# transceiver.net
KiCad netlist of a schematic drawn in EAGLE
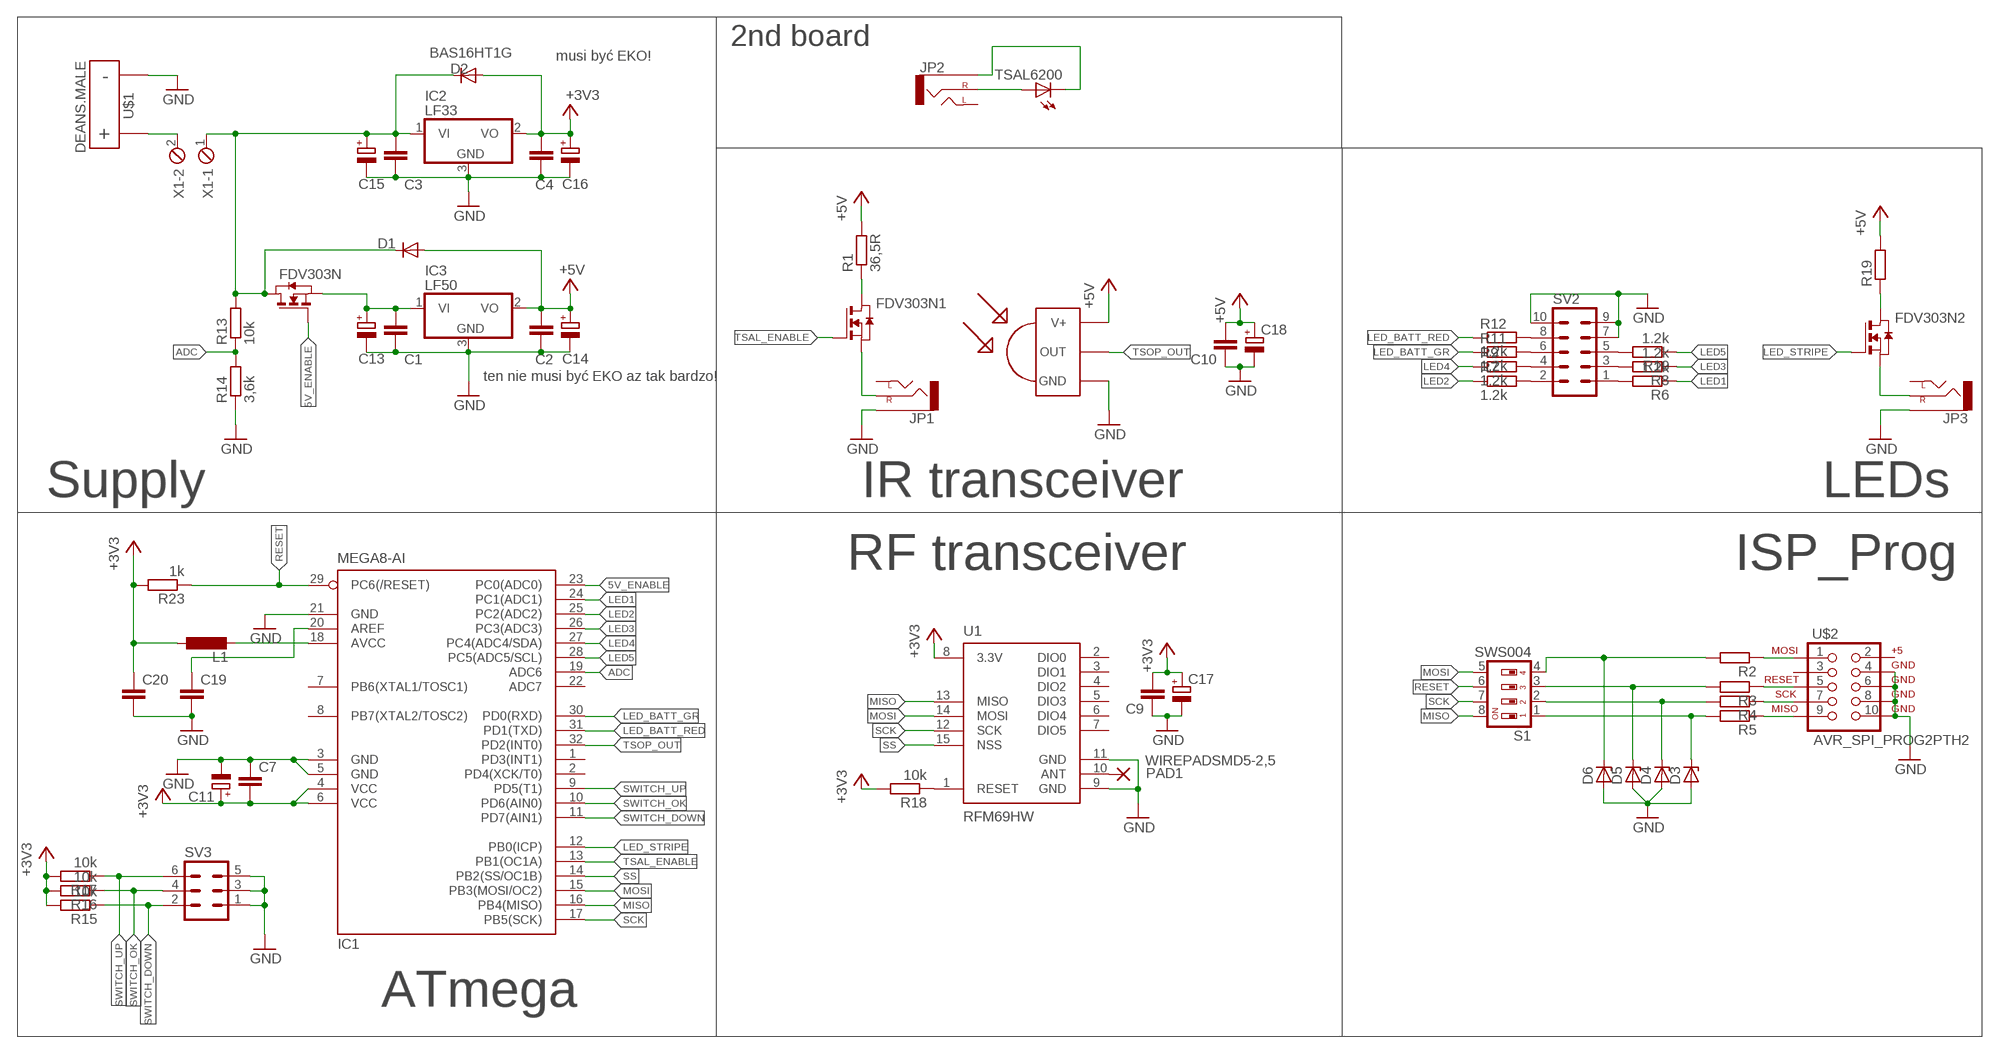
[diagram p0: schematic, sheet 1]

(export (version "E")
  (design (tool "Eeschema 10.0.6"))
  (components
    (comp (ref "C1")
      (value "C-EUC0805")
      (footprint "eagle-import:C0805")
      (libsource (lib "eagle-import") (part "C-EUC0805"))
    )
    (comp (ref "C2")
      (value "C-EUC0805")
      (footprint "eagle-import:C0805")
      (libsource (lib "eagle-import") (part "C-EUC0805"))
    )
    (comp (ref "C3")
      (value "C-EUC0805")
      (footprint "eagle-import:C0805")
      (libsource (lib "eagle-import") (part "C-EUC0805"))
    )
    (comp (ref "C4")
      (value "C-EUC0805")
      (footprint "eagle-import:C0805")
      (libsource (lib "eagle-import") (part "C-EUC0805"))
    )
    (comp (ref "C7")
      (value "C-EUC0805")
      (footprint "eagle-import:C0805")
      (libsource (lib "eagle-import") (part "C-EUC0805"))
    )
    (comp (ref "C9")
      (value "C-EUC0805")
      (footprint "eagle-import:C0805")
      (libsource (lib "eagle-import") (part "C-EUC0805"))
    )
    (comp (ref "C10")
      (value "C-EUC0805")
      (footprint "eagle-import:C0805")
      (libsource (lib "eagle-import") (part "C-EUC0805"))
    )
    (comp (ref "C11")
      (value "CPOL-EUE2.5-5")
      (footprint "eagle-import:E2,5-5")
      (libsource (lib "eagle-import") (part "CPOL-EUE2.5-5"))
    )
    (comp (ref "C13")
      (value "CPOL-EUE2.5-5")
      (footprint "eagle-import:E2,5-5")
      (libsource (lib "eagle-import") (part "CPOL-EUE2.5-5"))
    )
    (comp (ref "C14")
      (value "CPOL-EUE2.5-5")
      (footprint "eagle-import:E2,5-5")
      (libsource (lib "eagle-import") (part "CPOL-EUE2.5-5"))
    )
    (comp (ref "C15")
      (value "CPOL-EUE2.5-5")
      (footprint "eagle-import:E2,5-5")
      (libsource (lib "eagle-import") (part "CPOL-EUE2.5-5"))
    )
    (comp (ref "C16")
      (value "CPOL-EUE2.5-5")
      (footprint "eagle-import:E2,5-5")
      (libsource (lib "eagle-import") (part "CPOL-EUE2.5-5"))
    )
    (comp (ref "C17")
      (value "CPOL-EUE2.5-5")
      (footprint "eagle-import:E2,5-5")
      (libsource (lib "eagle-import") (part "CPOL-EUE2.5-5"))
    )
    (comp (ref "C18")
      (value "CPOL-EUE2.5-5")
      (footprint "eagle-import:E2,5-5")
      (libsource (lib "eagle-import") (part "CPOL-EUE2.5-5"))
    )
    (comp (ref "C19")
      (value "C-EUC0805")
      (footprint "eagle-import:C0805")
      (libsource (lib "eagle-import") (part "C-EUC0805"))
    )
    (comp (ref "C20")
      (value "C-EUC0805")
      (footprint "eagle-import:C0805")
      (libsource (lib "eagle-import") (part "C-EUC0805"))
    )
    (comp (ref "D1")
      (value "BAS16HT1G")
      (footprint "eagle-import:SOD-323")
      (libsource (lib "eagle-import") (part "DIODESOD"))
    )
    (comp (ref "D2")
      (value "BAS16HT1G")
      (footprint "eagle-import:SOD-323")
      (libsource (lib "eagle-import") (part "DIODESOD"))
    )
    (comp (ref "D3")
      (value "ZENER-DIODESOD80C")
      (footprint "eagle-import:SOD80C")
      (libsource (lib "eagle-import") (part "ZENER-DIODESOD80C"))
    )
    (comp (ref "D4")
      (value "ZENER-DIODESOD80C")
      (footprint "eagle-import:SOD80C")
      (libsource (lib "eagle-import") (part "ZENER-DIODESOD80C"))
    )
    (comp (ref "D5")
      (value "ZENER-DIODESOD80C")
      (footprint "eagle-import:SOD80C")
      (libsource (lib "eagle-import") (part "ZENER-DIODESOD80C"))
    )
    (comp (ref "D6")
      (value "ZENER-DIODESOD80C")
      (footprint "eagle-import:SOD80C")
      (libsource (lib "eagle-import") (part "ZENER-DIODESOD80C"))
    )
    (comp (ref "FDV303N")
      (value "NMOSSOT23")
      (footprint "eagle-import:SOT-23")
      (libsource (lib "eagle-import") (part "NMOSSOT23"))
    )
    (comp (ref "FDV303N1")
      (value "NMOSSOT23")
      (footprint "eagle-import:SOT-23")
      (libsource (lib "eagle-import") (part "NMOSSOT23"))
    )
    (comp (ref "FDV303N2")
      (value "NMOSSOT23")
      (footprint "eagle-import:SOT-23")
      (libsource (lib "eagle-import") (part "NMOSSOT23"))
    )
    (comp (ref "IC1")
      (value "MEGA8-AI")
      (footprint "eagle-import:TQFP32-08")
      (fields (field (name "MPN") "ATMEGA8-16AU"))
      (libsource (lib "eagle-import") (part "MEGA8-AI"))
    )
    (comp (ref "IC2")
      (value "LF33")
      (footprint "eagle-import:TO252")
      (libsource (lib "eagle-import") (part "78DT05"))
    )
    (comp (ref "IC3")
      (value "LF50")
      (footprint "eagle-import:TO252")
      (libsource (lib "eagle-import") (part "78DT05"))
    )
    (comp (ref "JP1")
      (value "AUDIO-JACKPTH")
      (footprint "eagle-import:AUDIO-JACK")
      (libsource (lib "eagle-import") (part "AUDIO-JACKPTH"))
    )
    (comp (ref "JP2")
      (value "AUDIO-JACKPTH")
      (footprint "eagle-import:AUDIO-JACK")
      (libsource (lib "eagle-import") (part "AUDIO-JACKPTH"))
    )
    (comp (ref "JP3")
      (value "AUDIO-JACKPTH")
      (footprint "eagle-import:AUDIO-JACK")
      (libsource (lib "eagle-import") (part "AUDIO-JACKPTH"))
    )
    (comp (ref "L1")
      (value "L-EU0204V")
      (footprint "eagle-import:0204V")
      (libsource (lib "eagle-import") (part "L-EU0204V"))
    )
    (comp (ref "PAD1")
      (value "WIREPADSMD5-2,5")
      (footprint "eagle-import:5-2,5")
      (libsource (lib "eagle-import") (part "WIREPADSMD5-2,5"))
    )
    (comp (ref "R1")
      (value "36,5R")
      (footprint "eagle-import:R0805")
      (libsource (lib "eagle-import") (part "R-EU_R0805"))
    )
    (comp (ref "R2")
      (value "R-EU_R0805")
      (footprint "eagle-import:R0805")
      (libsource (lib "eagle-import") (part "R-EU_R0805"))
    )
    (comp (ref "R3")
      (value "R-EU_R0805")
      (footprint "eagle-import:R0805")
      (libsource (lib "eagle-import") (part "R-EU_R0805"))
    )
    (comp (ref "R4")
      (value "R-EU_R0805")
      (footprint "eagle-import:R0805")
      (libsource (lib "eagle-import") (part "R-EU_R0805"))
    )
    (comp (ref "R5")
      (value "R-EU_R0805")
      (footprint "eagle-import:R0805")
      (libsource (lib "eagle-import") (part "R-EU_R0805"))
    )
    (comp (ref "R6")
      (value "1.2k")
      (footprint "eagle-import:R0805")
      (libsource (lib "eagle-import") (part "R-EU_R0805"))
    )
    (comp (ref "R7")
      (value "1.2k")
      (footprint "eagle-import:R0805")
      (libsource (lib "eagle-import") (part "R-EU_R0805"))
    )
    (comp (ref "R8")
      (value "1.2k")
      (footprint "eagle-import:R0805")
      (libsource (lib "eagle-import") (part "R-EU_R0805"))
    )
    (comp (ref "R9")
      (value "1.2k")
      (footprint "eagle-import:R0805")
      (libsource (lib "eagle-import") (part "R-EU_R0805"))
    )
    (comp (ref "R10")
      (value "1.2k")
      (footprint "eagle-import:R0805")
      (libsource (lib "eagle-import") (part "R-EU_R0805"))
    )
    (comp (ref "R11")
      (value "1,2k")
      (footprint "eagle-import:R0805")
      (libsource (lib "eagle-import") (part "R-EU_R0805"))
    )
    (comp (ref "R12")
      (value "1.2k")
      (footprint "eagle-import:R0805")
      (libsource (lib "eagle-import") (part "R-EU_R0805"))
    )
    (comp (ref "R13")
      (value "10k")
      (footprint "eagle-import:R0805")
      (libsource (lib "eagle-import") (part "R-EU_R0805"))
    )
    (comp (ref "R14")
      (value "3,6k")
      (footprint "eagle-import:R0805")
      (libsource (lib "eagle-import") (part "R-EU_R0805"))
    )
    (comp (ref "R15")
      (value "10k")
      (footprint "eagle-import:R0805")
      (libsource (lib "eagle-import") (part "R-EU_R0805"))
    )
    (comp (ref "R16")
      (value "10k")
      (footprint "eagle-import:R0805")
      (libsource (lib "eagle-import") (part "R-EU_R0805"))
    )
    (comp (ref "R17")
      (value "10k")
      (footprint "eagle-import:R0805")
      (libsource (lib "eagle-import") (part "R-EU_R0805"))
    )
    (comp (ref "R18")
      (value "10k")
      (footprint "eagle-import:R0805")
      (libsource (lib "eagle-import") (part "R-EU_R0805"))
    )
    (comp (ref "R19")
      (value "R-EU_R0805")
      (footprint "eagle-import:R0805")
      (libsource (lib "eagle-import") (part "R-EU_R0805"))
    )
    (comp (ref "R23")
      (value "1k")
      (footprint "eagle-import:R0805")
      (libsource (lib "eagle-import") (part "R-EU_R0805"))
    )
    (comp (ref "S1")
      (value "SWS004")
      (footprint "eagle-import:SMS-004")
      (libsource (lib "eagle-import") (part "SWS004"))
    )
    (comp (ref "SV2")
      (value "ML10")
      (footprint "eagle-import:ML10")
      (libsource (lib "eagle-import") (part "ML10"))
    )
    (comp (ref "SV3")
      (value "ML6")
      (footprint "eagle-import:ML6")
      (libsource (lib "eagle-import") (part "ML6"))
    )
    (comp (ref "TSAL6200")
      (value "LED5MM")
      (footprint "eagle-import:LED5MM")
      (libsource (lib "eagle-import") (part "LED5MM"))
    )
    (comp (ref "TSOP")
      (value "TSOP4836")
      (footprint "eagle-import:TSOP18XX")
      (libsource (lib "eagle-import") (part "TSOP4836"))
    )
    (comp (ref "U$1")
      (value "DEANS.MALE")
      (footprint "eagle-import:DEANSM")
      (libsource (lib "eagle-import") (part "DEANS.MALE"))
    )
    (comp (ref "U$2")
      (value "AVR_SPI_PROG2PTH2")
      (footprint "eagle-import:2X5-SHROUDED")
      (libsource (lib "eagle-import") (part "AVR_SPI_PROG2PTH2"))
    )
    (comp (ref "U1")
      (value "RFM69HW")
      (footprint "eagle-import:RFM69W-XXXS2")
      (libsource (lib "eagle-import") (part "RFM69HW"))
    )
    (comp (ref "X1")
      (value "MPT2")
      (footprint "eagle-import:2POL254")
      (libsource (lib "eagle-import") (part "MPT2"))
    )
  )
  (nets
    (net (code "1") (name "+3V3") (class "Default")
      (node (ref "C11") (pin "+") (pinfunction "+_+") (pintype "passive"))
      (node (ref "C16") (pin "+") (pinfunction "+_+") (pintype "passive"))
      (node (ref "C17") (pin "+") (pinfunction "+_+") (pintype "passive"))
      (node (ref "C20") (pin "1") (pinfunction "1_1") (pintype "passive"))
      (node (ref "C4") (pin "1") (pinfunction "1_1") (pintype "passive"))
      (node (ref "C7") (pin "2") (pinfunction "2_2") (pintype "passive"))
      (node (ref "C9") (pin "2") (pinfunction "2_2") (pintype "passive"))
      (node (ref "D2") (pin "2") (pinfunction "A_2") (pintype "passive"))
      (node (ref "IC1") (pin "4") (pinfunction "VCC_4") (pintype "power_in"))
      (node (ref "IC1") (pin "6") (pinfunction "VCC_6") (pintype "power_in"))
      (node (ref "IC2") (pin "2") (pinfunction "VO_2") (pintype "passive"))
      (node (ref "L1") (pin "1") (pinfunction "1_1") (pintype "passive"))
      (node (ref "R15") (pin "2") (pinfunction "2_2") (pintype "passive"))
      (node (ref "R16") (pin "2") (pinfunction "2_2") (pintype "passive"))
      (node (ref "R17") (pin "2") (pinfunction "2_2") (pintype "passive"))
      (node (ref "R18") (pin "2") (pinfunction "2_2") (pintype "passive"))
      (node (ref "R23") (pin "2") (pinfunction "2_2") (pintype "passive"))
      (node (ref "U1") (pin "8") (pinfunction "3.3V_8") (pintype "power_in"))
    )
    (net (code "2") (name "+5V") (class "Default")
      (node (ref "C10") (pin "2") (pinfunction "2_2") (pintype "passive"))
      (node (ref "C14") (pin "+") (pinfunction "+_+") (pintype "passive"))
      (node (ref "C18") (pin "+") (pinfunction "+_+") (pintype "passive"))
      (node (ref "C2") (pin "1") (pinfunction "1_1") (pintype "passive"))
      (node (ref "D1") (pin "2") (pinfunction "A_2") (pintype "passive"))
      (node (ref "IC3") (pin "2") (pinfunction "VO_2") (pintype "passive"))
      (node (ref "R1") (pin "2") (pinfunction "2_2") (pintype "passive"))
      (node (ref "R19") (pin "2") (pinfunction "2_2") (pintype "passive"))
      (node (ref "TSOP") (pin "VCC") (pinfunction "V+_VCC") (pintype "bidirectional"))
    )
    (net (code "3") (name "5V_ENABLE") (class "Default")
      (node (ref "FDV303N") (pin "3") (pinfunction "G_3") (pintype "passive"))
      (node (ref "IC1") (pin "23") (pinfunction "PC0(ADC0)_23") (pintype "bidirectional"))
    )
    (net (code "4") (name "ADC") (class "Default")
      (node (ref "IC1") (pin "19") (pinfunction "ADC6_19") (pintype "bidirectional"))
      (node (ref "R13") (pin "1") (pinfunction "1_1") (pintype "passive"))
      (node (ref "R14") (pin "2") (pinfunction "2_2") (pintype "passive"))
    )
    (net (code "5") (name "GND") (class "Default")
      (node (ref "C1") (pin "2") (pinfunction "2_2") (pintype "passive"))
      (node (ref "C10") (pin "1") (pinfunction "1_1") (pintype "passive"))
      (node (ref "C11") (pin "-") (pinfunction "-_-") (pintype "passive"))
      (node (ref "C13") (pin "-") (pinfunction "-_-") (pintype "passive"))
      (node (ref "C14") (pin "-") (pinfunction "-_-") (pintype "passive"))
      (node (ref "C15") (pin "-") (pinfunction "-_-") (pintype "passive"))
      (node (ref "C16") (pin "-") (pinfunction "-_-") (pintype "passive"))
      (node (ref "C17") (pin "-") (pinfunction "-_-") (pintype "passive"))
      (node (ref "C18") (pin "-") (pinfunction "-_-") (pintype "passive"))
      (node (ref "C19") (pin "2") (pinfunction "2_2") (pintype "passive"))
      (node (ref "C2") (pin "2") (pinfunction "2_2") (pintype "passive"))
      (node (ref "C20") (pin "2") (pinfunction "2_2") (pintype "passive"))
      (node (ref "C3") (pin "2") (pinfunction "2_2") (pintype "passive"))
      (node (ref "C4") (pin "2") (pinfunction "2_2") (pintype "passive"))
      (node (ref "C7") (pin "1") (pinfunction "1_1") (pintype "passive"))
      (node (ref "C9") (pin "1") (pinfunction "1_1") (pintype "passive"))
      (node (ref "D3") (pin "A") (pinfunction "A_A") (pintype "passive"))
      (node (ref "D4") (pin "A") (pinfunction "A_A") (pintype "passive"))
      (node (ref "D5") (pin "A") (pinfunction "A_A") (pintype "passive"))
      (node (ref "D6") (pin "A") (pinfunction "A_A") (pintype "passive"))
      (node (ref "IC1") (pin "21") (pinfunction "GND_21") (pintype "power_in"))
      (node (ref "IC1") (pin "3") (pinfunction "GND_3") (pintype "power_in"))
      (node (ref "IC1") (pin "5") (pinfunction "GND_5") (pintype "power_in"))
      (node (ref "IC2") (pin "3") (pinfunction "GND_3") (pintype "passive"))
      (node (ref "IC3") (pin "3") (pinfunction "GND_3") (pintype "passive"))
      (node (ref "JP1") (pin "SLEEVE") (pinfunction "SLEEVE_SLEEVE") (pintype "bidirectional"))
      (node (ref "JP3") (pin "SLEEVE") (pinfunction "SLEEVE_SLEEVE") (pintype "bidirectional"))
      (node (ref "R14") (pin "1") (pinfunction "1_1") (pintype "passive"))
      (node (ref "SV2") (pin "10") (pinfunction "10_10") (pintype "passive"))
      (node (ref "SV2") (pin "7") (pinfunction "7_7") (pintype "passive"))
      (node (ref "SV2") (pin "9") (pinfunction "9_9") (pintype "passive"))
      (node (ref "SV3") (pin "1") (pinfunction "1_1") (pintype "passive"))
      (node (ref "SV3") (pin "3") (pinfunction "3_3") (pintype "passive"))
      (node (ref "SV3") (pin "5") (pinfunction "5_5") (pintype "passive"))
      (node (ref "TSOP") (pin "GND") (pinfunction "GND_GND") (pintype "bidirectional"))
      (node (ref "U$1") (pin "P$NEG") (pinfunction "P$NEG_P$NEG") (pintype "bidirectional"))
      (node (ref "U$2") (pin "10") (pinfunction "10_10") (pintype "passive"))
      (node (ref "U$2") (pin "4") (pinfunction "4_4") (pintype "passive"))
      (node (ref "U$2") (pin "6") (pinfunction "6_6") (pintype "passive"))
      (node (ref "U$2") (pin "8") (pinfunction "8_8") (pintype "passive"))
      (node (ref "U1") (pin "11") (pinfunction "GND_11") (pintype "power_in"))
      (node (ref "U1") (pin "9") (pinfunction "GND_9") (pintype "power_in"))
    )
    (net (code "6") (name "LED1") (class "Default")
      (node (ref "IC1") (pin "24") (pinfunction "PC1(ADC1)_24") (pintype "bidirectional"))
      (node (ref "R6") (pin "1") (pinfunction "1_1") (pintype "passive"))
    )
    (net (code "7") (name "LED2") (class "Default")
      (node (ref "IC1") (pin "25") (pinfunction "PC2(ADC2)_25") (pintype "bidirectional"))
      (node (ref "R7") (pin "1") (pinfunction "1_1") (pintype "passive"))
    )
    (net (code "8") (name "LED3") (class "Default")
      (node (ref "IC1") (pin "26") (pinfunction "PC3(ADC3)_26") (pintype "bidirectional"))
      (node (ref "R8") (pin "1") (pinfunction "1_1") (pintype "passive"))
    )
    (net (code "9") (name "LED4") (class "Default")
      (node (ref "IC1") (pin "27") (pinfunction "PC4(ADC4/SDA)_27") (pintype "bidirectional"))
      (node (ref "R9") (pin "1") (pinfunction "1_1") (pintype "passive"))
    )
    (net (code "10") (name "LED5") (class "Default")
      (node (ref "IC1") (pin "28") (pinfunction "PC5(ADC5/SCL)_28") (pintype "bidirectional"))
      (node (ref "R10") (pin "1") (pinfunction "1_1") (pintype "passive"))
    )
    (net (code "11") (name "LED_BATT_GR") (class "Default")
      (node (ref "IC1") (pin "30") (pinfunction "PD0(RXD)_30") (pintype "bidirectional"))
      (node (ref "R11") (pin "1") (pinfunction "1_1") (pintype "passive"))
    )
    (net (code "12") (name "LED_BATT_RED") (class "Default")
      (node (ref "IC1") (pin "31") (pinfunction "PD1(TXD)_31") (pintype "bidirectional"))
      (node (ref "R12") (pin "1") (pinfunction "1_1") (pintype "passive"))
    )
    (net (code "13") (name "LED_STRIPE") (class "Default")
      (node (ref "FDV303N2") (pin "3") (pinfunction "G_3") (pintype "passive"))
      (node (ref "IC1") (pin "12") (pinfunction "PB0(ICP)_12") (pintype "bidirectional"))
    )
    (net (code "14") (name "MISO") (class "Default")
      (node (ref "IC1") (pin "16") (pinfunction "PB4(MISO)_16") (pintype "bidirectional"))
      (node (ref "S1") (pin "8") (pinfunction "8_8") (pintype "passive"))
      (node (ref "U1") (pin "13") (pinfunction "MISO_13") (pintype "bidirectional"))
    )
    (net (code "15") (name "MOSI") (class "Default")
      (node (ref "IC1") (pin "15") (pinfunction "PB3(MOSI/OC2)_15") (pintype "bidirectional"))
      (node (ref "S1") (pin "5") (pinfunction "5_5") (pintype "passive"))
      (node (ref "U1") (pin "14") (pinfunction "MOSI_14") (pintype "input"))
    )
    (net (code "16") (name "Net-(D1-C)") (class "Default")
      (node (ref "C15") (pin "+") (pinfunction "+_+") (pintype "passive"))
      (node (ref "C3") (pin "1") (pinfunction "1_1") (pintype "passive"))
      (node (ref "D1") (pin "1") (pinfunction "C_1") (pintype "passive"))
      (node (ref "D2") (pin "1") (pinfunction "C_1") (pintype "passive"))
      (node (ref "FDV303N") (pin "1") (pinfunction "D_1") (pintype "passive"))
      (node (ref "IC2") (pin "1") (pinfunction "VI_1") (pintype "input"))
      (node (ref "R13") (pin "2") (pinfunction "2_2") (pintype "passive"))
      (node (ref "X1") (pin "1") (pinfunction "1_1") (pintype "passive"))
    )
    (net (code "17") (name "Net-(D3-PadC)") (class "Default")
      (node (ref "D3") (pin "C") (pinfunction "C_C") (pintype "passive"))
      (node (ref "R5") (pin "2") (pinfunction "2_2") (pintype "passive"))
      (node (ref "S1") (pin "1") (pinfunction "1_1") (pintype "passive"))
    )
    (net (code "18") (name "Net-(D4-PadC)") (class "Default")
      (node (ref "D4") (pin "C") (pinfunction "C_C") (pintype "passive"))
      (node (ref "R4") (pin "2") (pinfunction "2_2") (pintype "passive"))
      (node (ref "S1") (pin "2") (pinfunction "2_2") (pintype "passive"))
    )
    (net (code "19") (name "Net-(D5-PadC)") (class "Default")
      (node (ref "D5") (pin "C") (pinfunction "C_C") (pintype "passive"))
      (node (ref "R3") (pin "2") (pinfunction "2_2") (pintype "passive"))
      (node (ref "S1") (pin "3") (pinfunction "3_3") (pintype "passive"))
    )
    (net (code "20") (name "Net-(D6-PadC)") (class "Default")
      (node (ref "D6") (pin "C") (pinfunction "C_C") (pintype "passive"))
      (node (ref "R2") (pin "2") (pinfunction "2_2") (pintype "passive"))
      (node (ref "S1") (pin "4") (pinfunction "4_4") (pintype "passive"))
    )
    (net (code "21") (name "Net-(FDV303N-S)") (class "Default")
      (node (ref "C1") (pin "1") (pinfunction "1_1") (pintype "passive"))
      (node (ref "C13") (pin "+") (pinfunction "+_+") (pintype "passive"))
      (node (ref "FDV303N") (pin "2") (pinfunction "S_2") (pintype "passive"))
      (node (ref "IC3") (pin "1") (pinfunction "VI_1") (pintype "input"))
    )
    (net (code "22") (name "Net-(FDV303N1-D)") (class "Default")
      (node (ref "FDV303N1") (pin "1") (pinfunction "D_1") (pintype "passive"))
      (node (ref "R1") (pin "1") (pinfunction "1_1") (pintype "passive"))
    )
    (net (code "23") (name "Net-(FDV303N1-S)") (class "Default")
      (node (ref "FDV303N1") (pin "2") (pinfunction "S_2") (pintype "passive"))
      (node (ref "JP1") (pin "RING") (pinfunction "RIGHT_RING") (pintype "bidirectional"))
    )
    (net (code "24") (name "Net-(FDV303N2-D)") (class "Default")
      (node (ref "FDV303N2") (pin "1") (pinfunction "D_1") (pintype "passive"))
      (node (ref "R19") (pin "1") (pinfunction "1_1") (pintype "passive"))
    )
    (net (code "25") (name "Net-(FDV303N2-S)") (class "Default")
      (node (ref "FDV303N2") (pin "2") (pinfunction "S_2") (pintype "passive"))
      (node (ref "JP3") (pin "RING") (pinfunction "RIGHT_RING") (pintype "bidirectional"))
    )
    (net (code "26") (name "Net-(IC1-AREF)") (class "Default")
      (node (ref "C19") (pin "1") (pinfunction "1_1") (pintype "passive"))
      (node (ref "IC1") (pin "20") (pinfunction "AREF_20") (pintype "passive"))
    )
    (net (code "27") (name "Net-(IC1-AVCC)") (class "Default")
      (node (ref "IC1") (pin "18") (pinfunction "AVCC_18") (pintype "power_in"))
      (node (ref "L1") (pin "2") (pinfunction "2_2") (pintype "passive"))
    )
    (net (code "28") (name "Net-(JP2-RIGHT)") (class "Default")
      (node (ref "JP2") (pin "RING") (pinfunction "RIGHT_RING") (pintype "bidirectional"))
      (node (ref "TSAL6200") (pin "A") (pinfunction "A_A") (pintype "passive"))
    )
    (net (code "29") (name "Net-(PAD1-P)") (class "Default")
      (node (ref "PAD1") (pin "1") (pinfunction "P_1") (pintype "passive"))
      (node (ref "U1") (pin "10") (pinfunction "ANT_10") (pintype "passive"))
    )
    (net (code "30") (name "Net-(R2-Pad1)") (class "Default")
      (node (ref "R2") (pin "1") (pinfunction "1_1") (pintype "passive"))
      (node (ref "U$2") (pin "1") (pinfunction "1_1") (pintype "passive"))
    )
    (net (code "31") (name "Net-(R3-Pad1)") (class "Default")
      (node (ref "R3") (pin "1") (pinfunction "1_1") (pintype "passive"))
      (node (ref "U$2") (pin "5") (pinfunction "5_5") (pintype "passive"))
    )
    (net (code "32") (name "Net-(R4-Pad1)") (class "Default")
      (node (ref "R4") (pin "1") (pinfunction "1_1") (pintype "passive"))
      (node (ref "U$2") (pin "7") (pinfunction "7_7") (pintype "passive"))
    )
    (net (code "33") (name "Net-(R5-Pad1)") (class "Default")
      (node (ref "R5") (pin "1") (pinfunction "1_1") (pintype "passive"))
      (node (ref "U$2") (pin "9") (pinfunction "9_9") (pintype "passive"))
    )
    (net (code "34") (name "Net-(R6-Pad2)") (class "Default")
      (node (ref "R6") (pin "2") (pinfunction "2_2") (pintype "passive"))
      (node (ref "SV2") (pin "1") (pinfunction "1_1") (pintype "passive"))
    )
    (net (code "35") (name "Net-(R7-Pad2)") (class "Default")
      (node (ref "R7") (pin "2") (pinfunction "2_2") (pintype "passive"))
      (node (ref "SV2") (pin "2") (pinfunction "2_2") (pintype "passive"))
    )
    (net (code "36") (name "Net-(R8-Pad2)") (class "Default")
      (node (ref "R8") (pin "2") (pinfunction "2_2") (pintype "passive"))
      (node (ref "SV2") (pin "3") (pinfunction "3_3") (pintype "passive"))
    )
    (net (code "37") (name "Net-(R9-Pad2)") (class "Default")
      (node (ref "R9") (pin "2") (pinfunction "2_2") (pintype "passive"))
      (node (ref "SV2") (pin "4") (pinfunction "4_4") (pintype "passive"))
    )
    (net (code "38") (name "Net-(R10-Pad2)") (class "Default")
      (node (ref "R10") (pin "2") (pinfunction "2_2") (pintype "passive"))
      (node (ref "SV2") (pin "5") (pinfunction "5_5") (pintype "passive"))
    )
    (net (code "39") (name "Net-(R11-Pad2)") (class "Default")
      (node (ref "R11") (pin "2") (pinfunction "2_2") (pintype "passive"))
      (node (ref "SV2") (pin "6") (pinfunction "6_6") (pintype "passive"))
    )
    (net (code "40") (name "Net-(R12-Pad2)") (class "Default")
      (node (ref "R12") (pin "2") (pinfunction "2_2") (pintype "passive"))
      (node (ref "SV2") (pin "8") (pinfunction "8_8") (pintype "passive"))
    )
    (net (code "41") (name "Net-(TSAL6200-C)") (class "Default")
      (node (ref "JP2") (pin "SLEEVE") (pinfunction "SLEEVE_SLEEVE") (pintype "bidirectional"))
      (node (ref "TSAL6200") (pin "K") (pinfunction "C_K") (pintype "passive"))
    )
    (net (code "42") (name "Net-(U1-RESET)") (class "Default")
      (node (ref "R18") (pin "1") (pinfunction "1_1") (pintype "passive"))
      (node (ref "U1") (pin "1") (pinfunction "RESET_1") (pintype "input"))
    )
    (net (code "43") (name "Net-(X1B-1)") (class "Default")
      (node (ref "U$1") (pin "P$POS") (pinfunction "P$POS_P$POS") (pintype "bidirectional"))
      (node (ref "X1") (pin "2") (pinfunction "1_2") (pintype "passive"))
    )
    (net (code "44") (name "RESET") (class "Default")
      (node (ref "IC1") (pin "29") (pinfunction "PC6(/RESET)_29") (pintype "bidirectional"))
      (node (ref "R23") (pin "1") (pinfunction "1_1") (pintype "passive"))
      (node (ref "S1") (pin "6") (pinfunction "6_6") (pintype "passive"))
    )
    (net (code "45") (name "SCK") (class "Default")
      (node (ref "IC1") (pin "17") (pinfunction "PB5(SCK)_17") (pintype "bidirectional"))
      (node (ref "S1") (pin "7") (pinfunction "7_7") (pintype "passive"))
      (node (ref "U1") (pin "12") (pinfunction "SCK_12") (pintype "input"))
    )
    (net (code "46") (name "SS") (class "Default")
      (node (ref "IC1") (pin "14") (pinfunction "PB2(SS/OC1B)_14") (pintype "bidirectional"))
      (node (ref "U1") (pin "15") (pinfunction "NSS_15") (pintype "input"))
    )
    (net (code "47") (name "SWITCH_DOWN") (class "Default")
      (node (ref "IC1") (pin "11") (pinfunction "PD7(AIN1)_11") (pintype "bidirectional"))
      (node (ref "R15") (pin "1") (pinfunction "1_1") (pintype "passive"))
      (node (ref "SV3") (pin "2") (pinfunction "2_2") (pintype "passive"))
    )
    (net (code "48") (name "SWITCH_OK") (class "Default")
      (node (ref "IC1") (pin "10") (pinfunction "PD6(AIN0)_10") (pintype "bidirectional"))
      (node (ref "R16") (pin "1") (pinfunction "1_1") (pintype "passive"))
      (node (ref "SV3") (pin "4") (pinfunction "4_4") (pintype "passive"))
    )
    (net (code "49") (name "SWITCH_UP") (class "Default")
      (node (ref "IC1") (pin "9") (pinfunction "PD5(T1)_9") (pintype "bidirectional"))
      (node (ref "R17") (pin "1") (pinfunction "1_1") (pintype "passive"))
      (node (ref "SV3") (pin "6") (pinfunction "6_6") (pintype "passive"))
    )
    (net (code "50") (name "TSAL_ENABLE") (class "Default")
      (node (ref "FDV303N1") (pin "3") (pinfunction "G_3") (pintype "passive"))
      (node (ref "IC1") (pin "13") (pinfunction "PB1(OC1A)_13") (pintype "bidirectional"))
    )
    (net (code "51") (name "TSOP_OUT") (class "Default")
      (node (ref "IC1") (pin "32") (pinfunction "PD2(INT0)_32") (pintype "bidirectional"))
      (node (ref "TSOP") (pin "OUT") (pinfunction "OUT_OUT") (pintype "bidirectional"))
    )
    (net (code "52") (name "unconnected-(IC1-ADC7-Pad22)") (class "Default")
      (node (ref "IC1") (pin "22") (pinfunction "ADC7_22") (pintype "bidirectional"))
    )
    (net (code "53") (name "unconnected-(IC1-PB6(XTAL1{slash}TOSC1)-Pad7)") (class "Default")
      (node (ref "IC1") (pin "7") (pinfunction "PB6(XTAL1/TOSC1)_7") (pintype "bidirectional"))
    )
    (net (code "54") (name "unconnected-(IC1-PB7(XTAL2{slash}TOSC2)-Pad8)") (class "Default")
      (node (ref "IC1") (pin "8") (pinfunction "PB7(XTAL2/TOSC2)_8") (pintype "bidirectional"))
    )
    (net (code "55") (name "unconnected-(IC1-PD3(INT1)-Pad1)") (class "Default")
      (node (ref "IC1") (pin "1") (pinfunction "PD3(INT1)_1") (pintype "bidirectional"))
    )
    (net (code "56") (name "unconnected-(IC1-PD4(XCK{slash}T0)-Pad2)") (class "Default")
      (node (ref "IC1") (pin "2") (pinfunction "PD4(XCK/T0)_2") (pintype "bidirectional"))
    )
    (net (code "57") (name "unconnected-(JP1-LEFT-PadTIP)") (class "Default")
      (node (ref "JP1") (pin "TIP") (pinfunction "LEFT_TIP") (pintype "bidirectional"))
    )
    (net (code "58") (name "unconnected-(JP2-LEFT-PadTIP)") (class "Default")
      (node (ref "JP2") (pin "TIP") (pinfunction "LEFT_TIP") (pintype "bidirectional"))
    )
    (net (code "59") (name "unconnected-(JP3-LEFT-PadTIP)") (class "Default")
      (node (ref "JP3") (pin "TIP") (pinfunction "LEFT_TIP") (pintype "bidirectional"))
    )
    (net (code "60") (name "unconnected-(U$2-Pad2)") (class "Default")
      (node (ref "U$2") (pin "2") (pinfunction "2_2") (pintype "passive"))
    )
    (net (code "61") (name "unconnected-(U$2-Pad3)") (class "Default")
      (node (ref "U$2") (pin "3") (pinfunction "3_3") (pintype "passive"))
    )
    (net (code "62") (name "unconnected-(U1-DIO0-Pad2)") (class "Default")
      (node (ref "U1") (pin "2") (pinfunction "DIO0_2") (pintype "bidirectional"))
    )
    (net (code "63") (name "unconnected-(U1-DIO1-Pad3)") (class "Default")
      (node (ref "U1") (pin "3") (pinfunction "DIO1_3") (pintype "bidirectional"))
    )
    (net (code "64") (name "unconnected-(U1-DIO2-Pad4)") (class "Default")
      (node (ref "U1") (pin "4") (pinfunction "DIO2_4") (pintype "bidirectional"))
    )
    (net (code "65") (name "unconnected-(U1-DIO3-Pad5)") (class "Default")
      (node (ref "U1") (pin "5") (pinfunction "DIO3_5") (pintype "bidirectional"))
    )
    (net (code "66") (name "unconnected-(U1-DIO4-Pad6)") (class "Default")
      (node (ref "U1") (pin "6") (pinfunction "DIO4_6") (pintype "bidirectional"))
    )
    (net (code "67") (name "unconnected-(U1-DIO5-Pad7)") (class "Default")
      (node (ref "U1") (pin "7") (pinfunction "DIO5_7") (pintype "bidirectional"))
    )
  )
)
